# Tracking-Car.net
KiCad netlist of a schematic drawn in Altium Designer
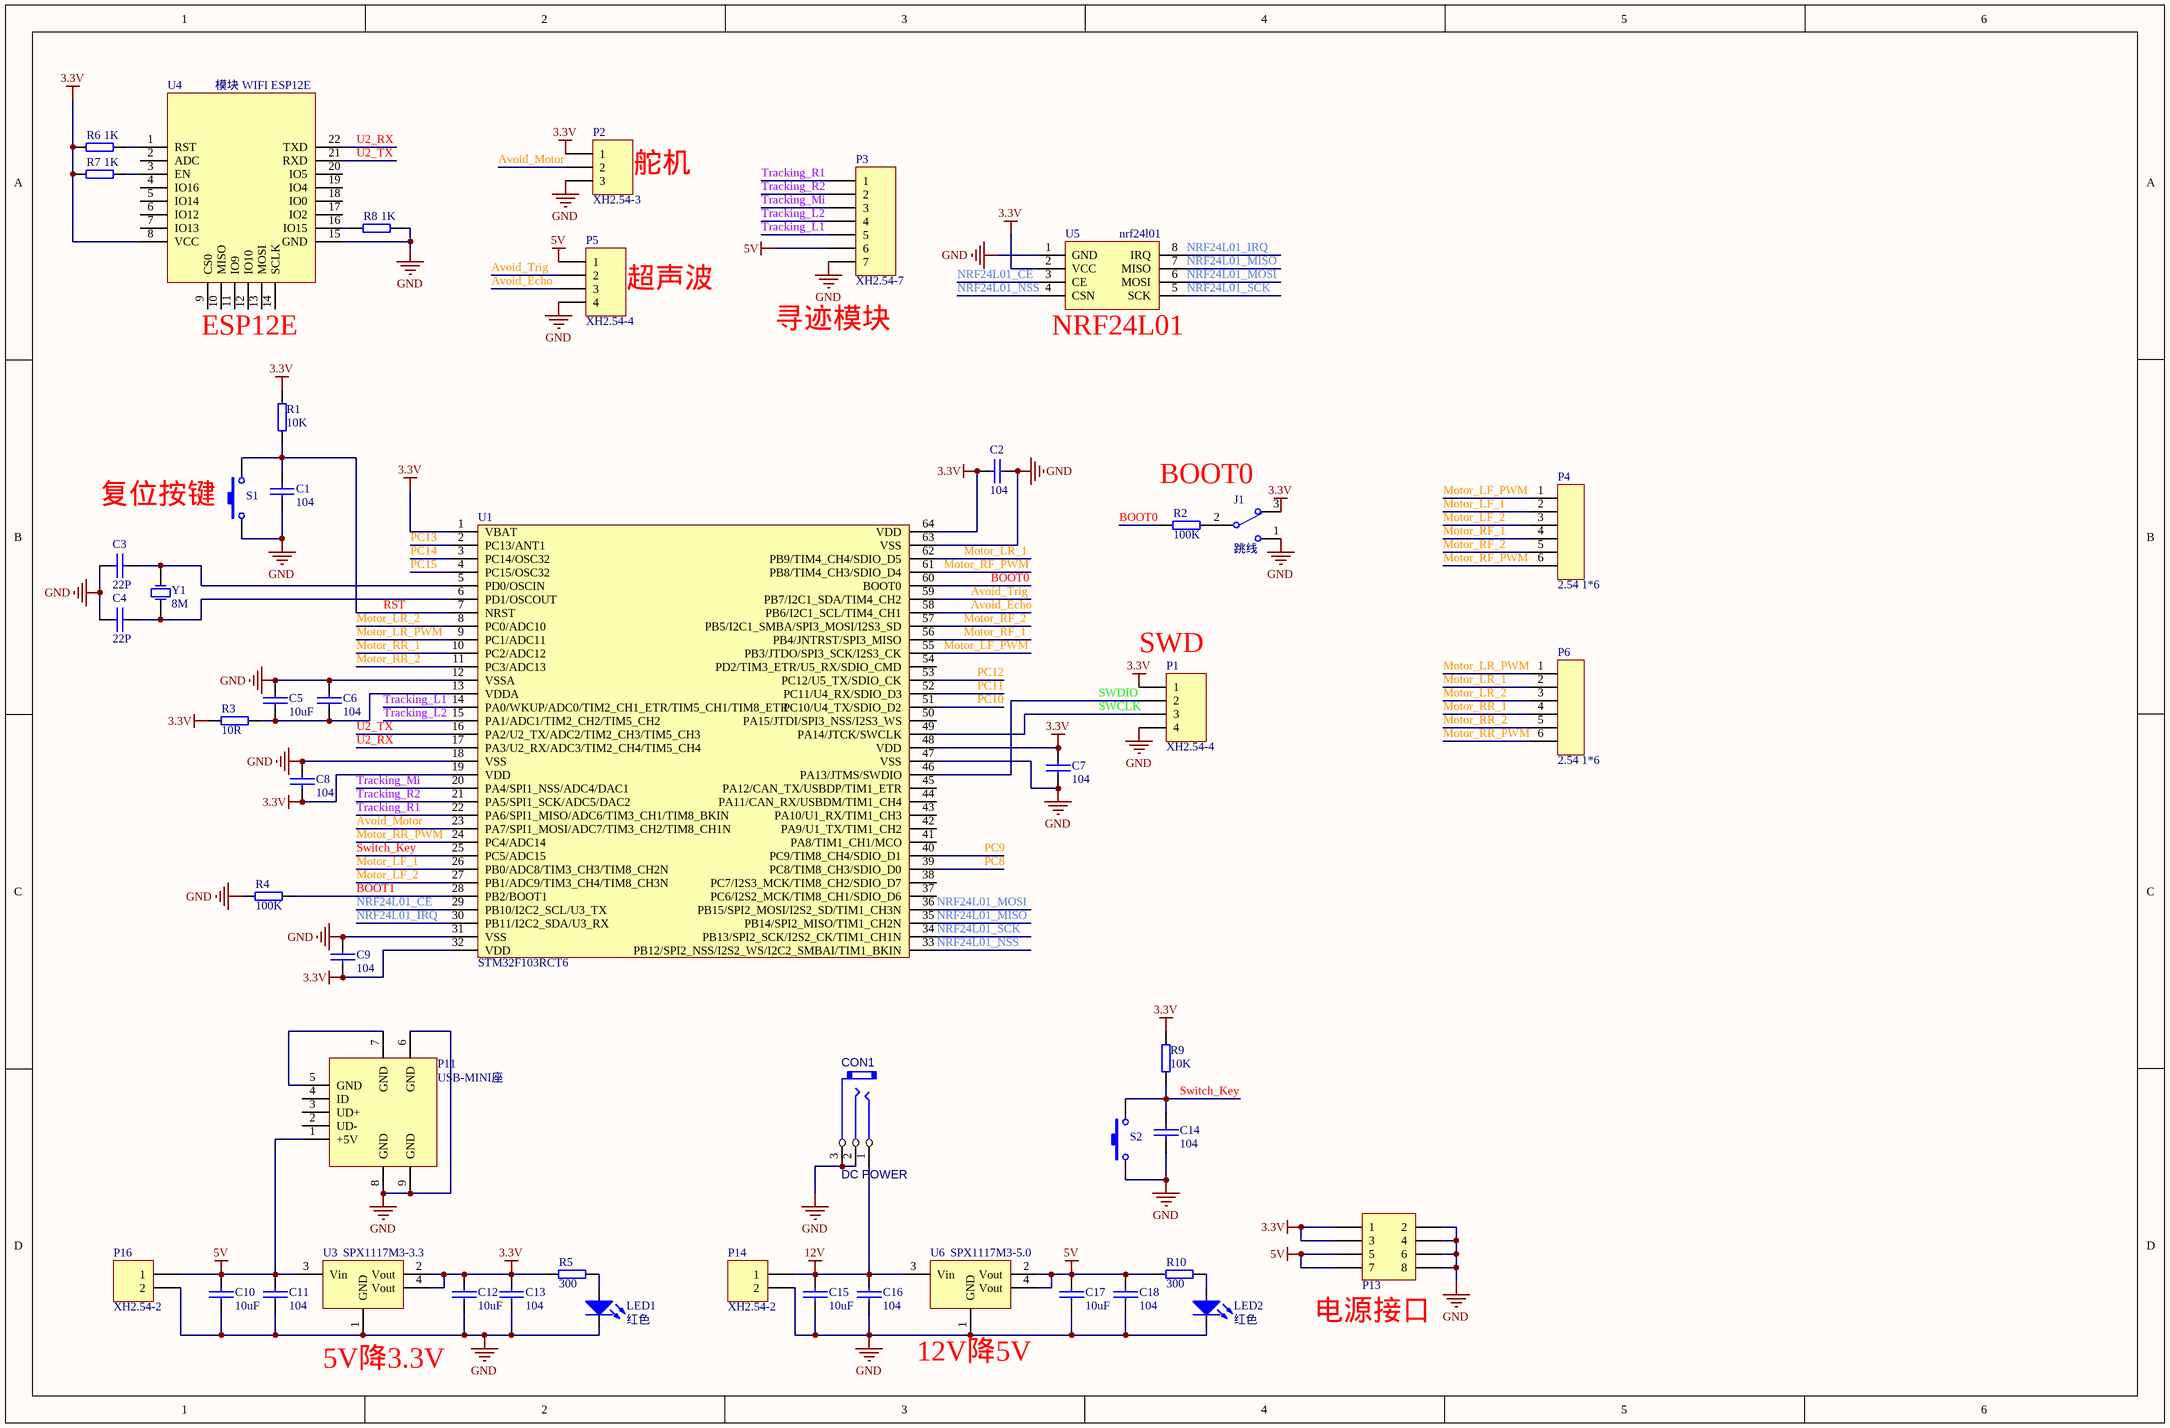
[diagram p0: Tracking-Car.SchDoc]

(export (version "E")
  (design (tool "Eeschema 10.0.6"))
  (components
    (comp (ref "C1")
      (value "104")
      (footprint "0805")
      (libsource (lib "Sch_Device_veryaz") (part "电容 贴片 0805"))
    )
    (comp (ref "C2")
      (value "104")
      (footprint "0805")
      (libsource (lib "Sch_Device_veryaz") (part "电容 贴片 0805"))
    )
    (comp (ref "C3")
      (value "22P")
      (footprint "0805")
      (libsource (lib "Sch_Device_veryaz") (part "电容 贴片 0805"))
    )
    (comp (ref "C4")
      (value "22P")
      (footprint "0805")
      (libsource (lib "Sch_Device_veryaz") (part "电容 贴片 0805"))
    )
    (comp (ref "C5")
      (value "10uF")
      (footprint "0805")
      (libsource (lib "Sch_Device_veryaz") (part "电容 贴片 0805"))
    )
    (comp (ref "C6")
      (value "104")
      (footprint "0805")
      (libsource (lib "Sch_Device_veryaz") (part "电容 贴片 0805"))
    )
    (comp (ref "C7")
      (value "104")
      (footprint "0805")
      (libsource (lib "Sch_Device_veryaz") (part "电容 贴片 0805"))
    )
    (comp (ref "C8")
      (value "104")
      (footprint "0805")
      (libsource (lib "Sch_Device_veryaz") (part "电容 贴片 0805"))
    )
    (comp (ref "C9")
      (value "104")
      (footprint "0805")
      (libsource (lib "Sch_Device_veryaz") (part "电容 贴片 0805"))
    )
    (comp (ref "C10")
      (value "10uF")
      (footprint "0805")
      (libsource (lib "Sch_Device_veryaz") (part "电容 贴片 0805"))
    )
    (comp (ref "C11")
      (value "104")
      (footprint "0805")
      (libsource (lib "Sch_Device_veryaz") (part "电容 贴片 0805"))
    )
    (comp (ref "C12")
      (value "10uF")
      (footprint "0805")
      (libsource (lib "Sch_Device_veryaz") (part "电容 贴片 0805"))
    )
    (comp (ref "C13")
      (value "104")
      (footprint "0805")
      (libsource (lib "Sch_Device_veryaz") (part "电容 贴片 0805"))
    )
    (comp (ref "C14")
      (value "104")
      (footprint "0805")
      (libsource (lib "Sch_Device_veryaz") (part "电容 贴片 0805"))
    )
    (comp (ref "C15")
      (value "10uF")
      (footprint "0805")
      (libsource (lib "Sch_Device_veryaz") (part "电容 贴片 0805"))
    )
    (comp (ref "C16")
      (value "104")
      (footprint "0805")
      (libsource (lib "Sch_Device_veryaz") (part "电容 贴片 0805"))
    )
    (comp (ref "C17")
      (value "10uF")
      (footprint "0805")
      (libsource (lib "Sch_Device_veryaz") (part "电容 贴片 0805"))
    )
    (comp (ref "C18")
      (value "104")
      (footprint "0805")
      (libsource (lib "Sch_Device_veryaz") (part "电容 贴片 0805"))
    )
    (comp (ref "CON1")
      (value "DC POWER")
      (footprint "Power  2.1mm")
      (libsource (lib "Sch_Device_veryaz") (part "连接件 电源座"))
    )
    (comp (ref "J1")
      (value "跳线")
      (footprint "单排插针 2.54 1*3")
      (libsource (lib "Sch_Device_veryaz") (part "联结件 跳线端子 2.54-3"))
    )
    (comp (ref "LED1")
      (value "红色")
      (footprint "LED0805")
      (libsource (lib "Sch_Device_veryaz") (part "二极管 贴片发光 0805"))
    )
    (comp (ref "LED2")
      (value "红色")
      (footprint "LED0805")
      (libsource (lib "Sch_Device_veryaz") (part "二极管 贴片发光 0805"))
    )
    (comp (ref "P1")
      (value "XH2.54-4")
      (footprint "VH2.54_4")
      (libsource (lib "Sch_Device_veryaz") (part "联结件 XH2.54-4"))
    )
    (comp (ref "P2")
      (value "XH2.54-3")
      (footprint "单排插针 2.54 1*3")
      (libsource (lib "Sch_Device_veryaz") (part "连接件 XH2.54-3"))
    )
    (comp (ref "P3")
      (value "XH2.54-7")
      (footprint "VH2.54_7")
      (libsource (lib "Sch_Device_veryaz") (part "连接件 XH2.54-7"))
    )
    (comp (ref "P4")
      (value "2.54 1*6")
      (footprint "单排插针 2.54 1*6")
      (libsource (lib "Sch_Device_veryaz") (part "连接件 单排插针 2.54 1*6"))
    )
    (comp (ref "P5")
      (value "XH2.54-4")
      (footprint "VH2.54_4")
      (libsource (lib "Sch_Device_veryaz") (part "联结件 XH2.54-4"))
    )
    (comp (ref "P6")
      (value "2.54 1*6")
      (footprint "单排插针 2.54 1*6")
      (libsource (lib "Sch_Device_veryaz") (part "连接件 单排插针 2.54 1*6"))
    )
    (comp (ref "P11")
      (value "USB-MINI座")
      (footprint "USB MINI DIP")
      (libsource (lib "Sch_Device_veryaz") (part "联结件 USB-MINI座"))
    )
    (comp (ref "P13")
      (value "双排插针 2.54 2*4")
      (footprint "双排插针 2.54 2*4")
      (libsource (lib "Sch_Device_veryaz") (part "联结件 双排插针 2.54 2*4"))
    )
    (comp (ref "P14")
      (value "XH2.54-2")
      (footprint "VH2.54_2")
      (libsource (lib "Sch_Device_veryaz") (part "联结件 XH2.54-2"))
    )
    (comp (ref "P16")
      (value "XH2.54-2")
      (footprint "VH2.54_2")
      (libsource (lib "Sch_Device_veryaz") (part "联结件 XH2.54-2"))
    )
    (comp (ref "R1") (value "10K") (footprint "0805") (libsource (lib "") (part "电阻 贴片 0805_1")))
    (comp (ref "R2")
      (value "100K")
      (footprint "0805")
      (libsource (lib "Sch_Device_veryaz") (part "电阻 贴片 0805"))
    )
    (comp (ref "R3")
      (value "10R")
      (footprint "0805")
      (libsource (lib "Sch_Device_veryaz") (part "电阻 贴片 0805"))
    )
    (comp (ref "R4")
      (value "100K")
      (footprint "0805")
      (libsource (lib "Sch_Device_veryaz") (part "电阻 贴片 0805"))
    )
    (comp (ref "R5")
      (value "300")
      (footprint "0805")
      (libsource (lib "Sch_Device_veryaz") (part "电阻 贴片 0805"))
    )
    (comp (ref "R6")
      (value "1K")
      (footprint "0805")
      (libsource (lib "Sch_Device_veryaz") (part "电阻 贴片 0805"))
    )
    (comp (ref "R7")
      (value "1K")
      (footprint "0805")
      (libsource (lib "Sch_Device_veryaz") (part "电阻 贴片 0805"))
    )
    (comp (ref "R8")
      (value "1K")
      (footprint "0805")
      (libsource (lib "Sch_Device_veryaz") (part "电阻 贴片 0805"))
    )
    (comp (ref "R9") (value "10K") (footprint "0805") (libsource (lib "") (part "电阻 贴片 0805_1")))
    (comp (ref "R10")
      (value "300")
      (footprint "0805")
      (libsource (lib "Sch_Device_veryaz") (part "电阻 贴片 0805"))
    )
    (comp (ref "S1")
      (value "key")
      (footprint "按键 轻触  6*3")
      (libsource (lib "Sch_Device_veryaz") (part "按键 轻触 3*6"))
    )
    (comp (ref "S2")
      (value "key")
      (footprint "按键 轻触  6*3")
      (libsource (lib "Sch_Device_veryaz") (part "按键 轻触 3*6"))
    )
    (comp (ref "U1")
      (value "STM32F103RCT6")
      (footprint "Pcb Device_veryaz:LQFP64")
      (description "单片机")
      (libsource (lib "Sch_Device_veryaz") (part "贴片芯片 STM32F103RCT6"))
    )
    (comp (ref "U3")
      (value "SPX1117M3-3.3")
      (footprint "SOT223")
      (description "LDO")
      (libsource (lib "Sch_Device_veryaz") (part "贴片芯片 SPX1117M3-3.3"))
    )
    (comp (ref "U4")
      (value "模块 WIFI ESP12E")
      (footprint "模块 WIFI ESP12E")
      (libsource (lib "Sch_Device_veryaz") (part "模块 WIFI ESP12E"))
    )
    (comp (ref "U5")
      (value "nrf24l01")
      (footprint "模块 NRF24L01")
      (libsource (lib "Sch_Device_veryaz") (part "模块 NRF24L01"))
    )
    (comp (ref "U6")
      (value "SPX1117M3-5.0")
      (footprint "SOT223")
      (description "LDO")
      (libsource (lib "Sch_Device_veryaz") (part "贴片芯片 SPX1117M3-5.0"))
    )
    (comp (ref "Y1")
      (value "8M")
      (footprint "晶振 BCY-W2/E4.7")
      (libsource (lib "Sch_Device_veryaz") (part "晶振 直插矮"))
    )
  )
  (nets
    (net (code "1") (name "/Avoid_Echo") (class "Default")
      (node (ref "P5") (pin "3") (pinfunction "3_3") (pintype "passive"))
      (node (ref "U1") (pin "58") (pinfunction "PB6/I2C1_SCL/TIM4_CH1_58") (pintype "passive"))
    )
    (net (code "2") (name "/Avoid_Motor") (class "Default")
      (node (ref "P2") (pin "2") (pinfunction "2_2") (pintype "passive"))
      (node (ref "U1") (pin "23") (pinfunction "PA7/SPI1_MOSI/ADC7/TIM3_CH2/TIM8_CH1N_23") (pintype "passive"))
    )
    (net (code "3") (name "/Avoid_Trig") (class "Default")
      (node (ref "P5") (pin "2") (pinfunction "2_2") (pintype "passive"))
      (node (ref "U1") (pin "59") (pinfunction "PB7/I2C1_SDA/TIM4_CH2_59") (pintype "passive"))
    )
    (net (code "4") (name "/BOOT0") (class "Default")
      (node (ref "R2") (pin "2") (pinfunction "2_2") (pintype "passive"))
      (node (ref "U1") (pin "60") (pinfunction "BOOT0_60") (pintype "passive"))
    )
    (net (code "5") (name "/BOOT1") (class "Default")
      (node (ref "R4") (pin "1") (pinfunction "1_1") (pintype "passive"))
      (node (ref "U1") (pin "28") (pinfunction "PB2/BOOT1_28") (pintype "passive"))
    )
    (net (code "6") (name "/Motor_LF_1") (class "Default")
      (node (ref "P4") (pin "2") (pinfunction "2_2") (pintype "passive"))
      (node (ref "U1") (pin "26") (pinfunction "PB0/ADC8/TIM3_CH3/TIM8_CH2N_26") (pintype "passive"))
    )
    (net (code "7") (name "/Motor_LF_2") (class "Default")
      (node (ref "P4") (pin "3") (pinfunction "3_3") (pintype "passive"))
      (node (ref "U1") (pin "27") (pinfunction "PB1/ADC9/TIM3_CH4/TIM8_CH3N_27") (pintype "passive"))
    )
    (net (code "8") (name "/Motor_LF_PWM") (class "Default")
      (node (ref "P4") (pin "1") (pinfunction "1_1") (pintype "passive"))
      (node (ref "U1") (pin "55") (pinfunction "PB3/JTDO/SPI3_SCK/I2S3_CK_55") (pintype "passive"))
    )
    (net (code "9") (name "/Motor_LR_1") (class "Default")
      (node (ref "P6") (pin "2") (pinfunction "2_2") (pintype "passive"))
      (node (ref "U1") (pin "62") (pinfunction "PB9/TIM4_CH4/SDIO_D5_62") (pintype "passive"))
    )
    (net (code "10") (name "/Motor_LR_2") (class "Default")
      (node (ref "P6") (pin "3") (pinfunction "3_3") (pintype "passive"))
      (node (ref "U1") (pin "8") (pinfunction "PC0/ADC10_8") (pintype "passive"))
    )
    (net (code "11") (name "/Motor_LR_PWM") (class "Default")
      (node (ref "P6") (pin "1") (pinfunction "1_1") (pintype "passive"))
      (node (ref "U1") (pin "9") (pinfunction "PC1/ADC11_9") (pintype "passive"))
    )
    (net (code "12") (name "/Motor_RF_1") (class "Default")
      (node (ref "P4") (pin "4") (pinfunction "4_4") (pintype "passive"))
      (node (ref "U1") (pin "56") (pinfunction "PB4/JNTRST/SPI3_MISO_56") (pintype "passive"))
    )
    (net (code "13") (name "/Motor_RF_2") (class "Default")
      (node (ref "P4") (pin "5") (pinfunction "5_5") (pintype "passive"))
      (node (ref "U1") (pin "57") (pinfunction "PB5/I2C1_SMBA/SPI3_MOSI/I2S3_SD_57") (pintype "passive"))
    )
    (net (code "14") (name "/Motor_RF_PWM") (class "Default")
      (node (ref "P4") (pin "6") (pinfunction "6_6") (pintype "passive"))
      (node (ref "U1") (pin "61") (pinfunction "PB8/TIM4_CH3/SDIO_D4_61") (pintype "passive"))
    )
    (net (code "15") (name "/Motor_RR_1") (class "Default")
      (node (ref "P6") (pin "4") (pinfunction "4_4") (pintype "passive"))
      (node (ref "U1") (pin "10") (pinfunction "PC2/ADC12_10") (pintype "passive"))
    )
    (net (code "16") (name "/Motor_RR_2") (class "Default")
      (node (ref "P6") (pin "5") (pinfunction "5_5") (pintype "passive"))
      (node (ref "U1") (pin "11") (pinfunction "PC3/ADC13_11") (pintype "passive"))
    )
    (net (code "17") (name "/Motor_RR_PWM") (class "Default")
      (node (ref "P6") (pin "6") (pinfunction "6_6") (pintype "passive"))
      (node (ref "U1") (pin "24") (pinfunction "PC4/ADC14_24") (pintype "passive"))
    )
    (net (code "18") (name "/NRF24L01_CE") (class "Default")
      (node (ref "U1") (pin "29") (pinfunction "PB10/I2C2_SCL/U3_TX_29") (pintype "passive"))
      (node (ref "U5") (pin "3") (pinfunction "CE_3") (pintype "passive"))
    )
    (net (code "19") (name "/NRF24L01_IRQ") (class "Default")
      (node (ref "U1") (pin "30") (pinfunction "PB11/I2C2_SDA/U3_RX_30") (pintype "passive"))
      (node (ref "U5") (pin "8") (pinfunction "IRQ_8") (pintype "passive"))
    )
    (net (code "20") (name "/NRF24L01_MISO") (class "Default")
      (node (ref "U1") (pin "35") (pinfunction "PB14/SPI2_MISO/TIM1_CH2N_35") (pintype "passive"))
      (node (ref "U5") (pin "7") (pinfunction "MISO_7") (pintype "passive"))
    )
    (net (code "21") (name "/NRF24L01_MOSI") (class "Default")
      (node (ref "U1") (pin "36") (pinfunction "PB15/SPI2_MOSI/I2S2_SD/TIM1_CH3N_36") (pintype "passive"))
      (node (ref "U5") (pin "6") (pinfunction "MOSI_6") (pintype "passive"))
    )
    (net (code "22") (name "/NRF24L01_NSS") (class "Default")
      (node (ref "U1") (pin "33") (pinfunction "PB12/SPI2_NSS/I2S2_WS/I2C2_SMBAI/TIM1_BKIN_33") (pintype "passive"))
      (node (ref "U5") (pin "4") (pinfunction "CSN_4") (pintype "passive"))
    )
    (net (code "23") (name "/NRF24L01_SCK") (class "Default")
      (node (ref "U1") (pin "34") (pinfunction "PB13/SPI2_SCK/I2S2_CK/TIM1_CH1N_34") (pintype "passive"))
      (node (ref "U5") (pin "5") (pinfunction "SCK_5") (pintype "passive"))
    )
    (net (code "24") (name "/PC8") (class "Default")
      (node (ref "U1") (pin "39") (pinfunction "PC8/TIM8_CH3/SDIO_D0_39") (pintype "passive"))
    )
    (net (code "25") (name "/PC9") (class "Default")
      (node (ref "U1") (pin "40") (pinfunction "PC9/TIM8_CH4/SDIO_D1_40") (pintype "passive"))
    )
    (net (code "26") (name "/PC10") (class "Default")
      (node (ref "U1") (pin "51") (pinfunction "PC10/U4_TX/SDIO_D2_51") (pintype "passive"))
    )
    (net (code "27") (name "/PC11") (class "Default")
      (node (ref "U1") (pin "52") (pinfunction "PC11/U4_RX/SDIO_D3_52") (pintype "passive"))
    )
    (net (code "28") (name "/PC12") (class "Default")
      (node (ref "U1") (pin "53") (pinfunction "PC12/U5_TX/SDIO_CK_53") (pintype "passive"))
    )
    (net (code "29") (name "/PC13") (class "Default")
      (node (ref "U1") (pin "2") (pinfunction "PC13/ANT1_2") (pintype "passive"))
    )
    (net (code "30") (name "/PC14") (class "Default")
      (node (ref "U1") (pin "3") (pinfunction "PC14/OSC32_3") (pintype "passive"))
    )
    (net (code "31") (name "/PC15") (class "Default")
      (node (ref "U1") (pin "4") (pinfunction "PC15/OSC32_4") (pintype "passive"))
    )
    (net (code "32") (name "/RST") (class "Default")
      (node (ref "C1") (pin "2") (pintype "passive"))
      (node (ref "R1") (pin "2") (pinfunction "2_2") (pintype "passive"))
      (node (ref "S1") (pin "2") (pinfunction "2_2") (pintype "passive"))
      (node (ref "U1") (pin "7") (pinfunction "NRST_7") (pintype "passive"))
    )
    (net (code "33") (name "/SWCLK") (class "Default")
      (node (ref "P1") (pin "3") (pinfunction "3_3") (pintype "passive"))
      (node (ref "U1") (pin "49") (pinfunction "PA14/JTCK/SWCLK_49") (pintype "passive"))
    )
    (net (code "34") (name "/SWDIO") (class "Default")
      (node (ref "P1") (pin "2") (pinfunction "2_2") (pintype "passive"))
      (node (ref "U1") (pin "46") (pinfunction "PA13/JTMS/SWDIO_46") (pintype "passive"))
    )
    (net (code "35") (name "/Switch_Key") (class "Default")
      (node (ref "C14") (pin "2") (pintype "passive"))
      (node (ref "R9") (pin "2") (pinfunction "2_2") (pintype "passive"))
      (node (ref "S2") (pin "2") (pinfunction "2_2") (pintype "passive"))
      (node (ref "U1") (pin "25") (pinfunction "PC5/ADC15_25") (pintype "passive"))
    )
    (net (code "36") (name "/Tracking_L1") (class "Default")
      (node (ref "P3") (pin "5") (pinfunction "5_5") (pintype "passive"))
      (node (ref "U1") (pin "14") (pinfunction "PA0/WKUP/ADC0/TIM2_CH1_ETR/TIM5_CH1/TIM8_ETR_14") (pintype "passive"))
    )
    (net (code "37") (name "/Tracking_L2") (class "Default")
      (node (ref "P3") (pin "4") (pinfunction "4_4") (pintype "passive"))
      (node (ref "U1") (pin "15") (pinfunction "PA1/ADC1/TIM2_CH2/TIM5_CH2_15") (pintype "passive"))
    )
    (net (code "38") (name "/Tracking_Mi") (class "Default")
      (node (ref "P3") (pin "3") (pinfunction "3_3") (pintype "passive"))
      (node (ref "U1") (pin "20") (pinfunction "PA4/SPI1_NSS/ADC4/DAC1_20") (pintype "passive"))
    )
    (net (code "39") (name "/Tracking_R1") (class "Default")
      (node (ref "P3") (pin "1") (pinfunction "1_1") (pintype "passive"))
      (node (ref "U1") (pin "22") (pinfunction "PA6/SPI1_MISO/ADC6/TIM3_CH1/TIM8_BKIN_22") (pintype "passive"))
    )
    (net (code "40") (name "/Tracking_R2") (class "Default")
      (node (ref "P3") (pin "2") (pinfunction "2_2") (pintype "passive"))
      (node (ref "U1") (pin "21") (pinfunction "PA5/SPI1_SCK/ADC5/DAC2_21") (pintype "passive"))
    )
    (net (code "41") (name "/U2_RX") (class "Default")
      (node (ref "U1") (pin "17") (pinfunction "PA3/U2_RX/ADC3/TIM2_CH4/TIM5_CH4_17") (pintype "passive"))
      (node (ref "U4") (pin "22") (pinfunction "TXD_22") (pintype "passive"))
    )
    (net (code "42") (name "/U2_TX") (class "Default")
      (node (ref "U1") (pin "16") (pinfunction "PA2/U2_TX/ADC2/TIM2_CH3/TIM5_CH3_16") (pintype "passive"))
      (node (ref "U4") (pin "21") (pinfunction "RXD_21") (pintype "passive"))
    )
    (net (code "43") (name "3.3V") (class "Default")
      (node (ref "C12") (pin "2") (pintype "passive"))
      (node (ref "C13") (pin "2") (pintype "passive"))
      (node (ref "C2") (pin "2") (pintype "passive"))
      (node (ref "C7") (pin "1") (pintype "passive"))
      (node (ref "C8") (pin "1") (pintype "passive"))
      (node (ref "C9") (pin "1") (pintype "passive"))
      (node (ref "J1") (pin "3") (pinfunction "3_3") (pintype "passive"))
      (node (ref "P1") (pin "1") (pinfunction "1_1") (pintype "passive"))
      (node (ref "P13") (pin "1") (pinfunction "1_1") (pintype "passive"))
      (node (ref "P13") (pin "3") (pinfunction "3_3") (pintype "passive"))
      (node (ref "P2") (pin "1") (pinfunction "1_1") (pintype "passive"))
      (node (ref "R1") (pin "1") (pinfunction "1_1") (pintype "passive"))
      (node (ref "R3") (pin "2") (pinfunction "2_2") (pintype "passive"))
      (node (ref "R5") (pin "2") (pinfunction "2_2") (pintype "passive"))
      (node (ref "R6") (pin "2") (pinfunction "2_2") (pintype "passive"))
      (node (ref "R7") (pin "2") (pinfunction "2_2") (pintype "passive"))
      (node (ref "R9") (pin "1") (pinfunction "1_1") (pintype "passive"))
      (node (ref "U1") (pin "1") (pinfunction "VBAT_1") (pintype "passive"))
      (node (ref "U1") (pin "19") (pinfunction "VDD_19") (pintype "passive"))
      (node (ref "U1") (pin "32") (pinfunction "VDD_32") (pintype "passive"))
      (node (ref "U1") (pin "48") (pinfunction "VDD_48") (pintype "passive"))
      (node (ref "U1") (pin "64") (pinfunction "VDD_64") (pintype "passive"))
      (node (ref "U3") (pin "2") (pinfunction "Vout_2") (pintype "passive"))
      (node (ref "U3") (pin "4") (pinfunction "Vout_4") (pintype "passive"))
      (node (ref "U4") (pin "8") (pinfunction "VCC_8") (pintype "passive"))
      (node (ref "U5") (pin "2") (pinfunction "VCC_2") (pintype "passive"))
    )
    (net (code "44") (name "5V") (class "Default")
      (node (ref "C10") (pin "2") (pintype "passive"))
      (node (ref "C11") (pin "2") (pintype "passive"))
      (node (ref "C17") (pin "2") (pintype "passive"))
      (node (ref "C18") (pin "2") (pintype "passive"))
      (node (ref "P11") (pin "1") (pinfunction "+5V_1") (pintype "passive"))
      (node (ref "P13") (pin "5") (pinfunction "5_5") (pintype "passive"))
      (node (ref "P13") (pin "7") (pinfunction "7_7") (pintype "passive"))
      (node (ref "P16") (pin "1") (pinfunction "1_1") (pintype "passive"))
      (node (ref "P3") (pin "6") (pinfunction "6_6") (pintype "passive"))
      (node (ref "P5") (pin "1") (pinfunction "1_1") (pintype "passive"))
      (node (ref "R10") (pin "2") (pinfunction "2_2") (pintype "passive"))
      (node (ref "U3") (pin "3") (pinfunction "Vin_3") (pintype "passive"))
      (node (ref "U6") (pin "2") (pinfunction "Vout_2") (pintype "passive"))
      (node (ref "U6") (pin "4") (pinfunction "Vout_4") (pintype "passive"))
    )
    (net (code "45") (name "12V") (class "Default")
      (node (ref "C15") (pin "2") (pintype "passive"))
      (node (ref "C16") (pin "2") (pintype "passive"))
      (node (ref "CON1") (pin "1") (pinfunction "1_1") (pintype "passive"))
      (node (ref "P14") (pin "1") (pinfunction "1_1") (pintype "passive"))
      (node (ref "U6") (pin "3") (pinfunction "Vin_3") (pintype "passive"))
    )
    (net (code "46") (name "GND") (class "Default")
      (node (ref "C1") (pin "1") (pintype "passive"))
      (node (ref "C10") (pin "1") (pintype "passive"))
      (node (ref "C11") (pin "1") (pintype "passive"))
      (node (ref "C12") (pin "1") (pintype "passive"))
      (node (ref "C13") (pin "1") (pintype "passive"))
      (node (ref "C14") (pin "1") (pintype "passive"))
      (node (ref "C15") (pin "1") (pintype "passive"))
      (node (ref "C16") (pin "1") (pintype "passive"))
      (node (ref "C17") (pin "1") (pintype "passive"))
      (node (ref "C18") (pin "1") (pintype "passive"))
      (node (ref "C2") (pin "1") (pintype "passive"))
      (node (ref "C3") (pin "1") (pintype "passive"))
      (node (ref "C4") (pin "1") (pintype "passive"))
      (node (ref "C5") (pin "2") (pintype "passive"))
      (node (ref "C6") (pin "2") (pintype "passive"))
      (node (ref "C7") (pin "2") (pintype "passive"))
      (node (ref "C8") (pin "2") (pintype "passive"))
      (node (ref "C9") (pin "2") (pintype "passive"))
      (node (ref "CON1") (pin "2") (pinfunction "2_2") (pintype "passive"))
      (node (ref "CON1") (pin "3") (pinfunction "3_3") (pintype "passive"))
      (node (ref "J1") (pin "1") (pinfunction "1_1") (pintype "passive"))
      (node (ref "LED1") (pin "2") (pinfunction "K_2") (pintype "passive"))
      (node (ref "LED2") (pin "2") (pinfunction "K_2") (pintype "passive"))
      (node (ref "P1") (pin "4") (pinfunction "4_4") (pintype "passive"))
      (node (ref "P11") (pin "6") (pinfunction "GND_6") (pintype "passive"))
      (node (ref "P11") (pin "8") (pinfunction "GND_8") (pintype "passive"))
      (node (ref "P11") (pin "9") (pinfunction "GND_9") (pintype "passive"))
      (node (ref "P13") (pin "2") (pinfunction "2_2") (pintype "passive"))
      (node (ref "P13") (pin "4") (pinfunction "4_4") (pintype "passive"))
      (node (ref "P13") (pin "6") (pinfunction "6_6") (pintype "passive"))
      (node (ref "P13") (pin "8") (pinfunction "8_8") (pintype "passive"))
      (node (ref "P14") (pin "2") (pinfunction "2_2") (pintype "passive"))
      (node (ref "P16") (pin "2") (pinfunction "2_2") (pintype "passive"))
      (node (ref "P2") (pin "3") (pinfunction "3_3") (pintype "passive"))
      (node (ref "P3") (pin "7") (pinfunction "7_7") (pintype "passive"))
      (node (ref "P5") (pin "4") (pinfunction "4_4") (pintype "passive"))
      (node (ref "R4") (pin "2") (pinfunction "2_2") (pintype "passive"))
      (node (ref "R8") (pin "1") (pinfunction "1_1") (pintype "passive"))
      (node (ref "S1") (pin "1") (pinfunction "1_1") (pintype "passive"))
      (node (ref "S2") (pin "1") (pinfunction "1_1") (pintype "passive"))
      (node (ref "U1") (pin "12") (pinfunction "VSSA_12") (pintype "passive"))
      (node (ref "U1") (pin "18") (pinfunction "VSS_18") (pintype "passive"))
      (node (ref "U1") (pin "31") (pinfunction "VSS_31") (pintype "passive"))
      (node (ref "U1") (pin "47") (pinfunction "VSS_47") (pintype "passive"))
      (node (ref "U1") (pin "63") (pinfunction "VSS_63") (pintype "passive"))
      (node (ref "U3") (pin "1") (pinfunction "GND_1") (pintype "passive"))
      (node (ref "U4") (pin "15") (pinfunction "GND_15") (pintype "passive"))
      (node (ref "U5") (pin "1") (pinfunction "GND_1") (pintype "passive"))
      (node (ref "U6") (pin "1") (pinfunction "GND_1") (pintype "passive"))
    )
    (net (code "47") (name "Net-(J1-Pad2)") (class "Default")
      (node (ref "J1") (pin "2") (pinfunction "2_2") (pintype "passive"))
      (node (ref "R2") (pin "1") (pinfunction "1_1") (pintype "passive"))
    )
    (net (code "48") (name "Net-(LED1-A)") (class "Default")
      (node (ref "LED1") (pin "1") (pinfunction "A_1") (pintype "passive"))
      (node (ref "R5") (pin "1") (pinfunction "1_1") (pintype "passive"))
    )
    (net (code "49") (name "Net-(LED2-A)") (class "Default")
      (node (ref "LED2") (pin "1") (pinfunction "A_1") (pintype "passive"))
      (node (ref "R10") (pin "1") (pinfunction "1_1") (pintype "passive"))
    )
    (net (code "50") (name "Net-(P11-GND-Pad5)") (class "Default")
      (node (ref "P11") (pin "5") (pinfunction "GND_5") (pintype "passive"))
      (node (ref "P11") (pin "7") (pinfunction "GND_7") (pintype "passive"))
    )
    (net (code "51") (name "Net-(U1-PD0{slash}OSCIN)") (class "Default")
      (node (ref "C3") (pin "2") (pintype "passive"))
      (node (ref "U1") (pin "5") (pinfunction "PD0/OSCIN_5") (pintype "passive"))
      (node (ref "Y1") (pin "2") (pinfunction "OSC2_2") (pintype "passive"))
    )
    (net (code "52") (name "Net-(U1-PD1{slash}OSCOUT)") (class "Default")
      (node (ref "C4") (pin "2") (pintype "passive"))
      (node (ref "U1") (pin "6") (pinfunction "PD1/OSCOUT_6") (pintype "passive"))
      (node (ref "Y1") (pin "1") (pinfunction "OSC1_1") (pintype "passive"))
    )
    (net (code "53") (name "Net-(U1-VDDA)") (class "Default")
      (node (ref "C5") (pin "1") (pintype "passive"))
      (node (ref "C6") (pin "1") (pintype "passive"))
      (node (ref "R3") (pin "1") (pinfunction "1_1") (pintype "passive"))
      (node (ref "U1") (pin "13") (pinfunction "VDDA_13") (pintype "passive"))
    )
    (net (code "54") (name "Net-(U4-EN)") (class "Default")
      (node (ref "R7") (pin "1") (pinfunction "1_1") (pintype "passive"))
      (node (ref "U4") (pin "3") (pinfunction "EN_3") (pintype "passive"))
    )
    (net (code "55") (name "Net-(U4-IO15)") (class "Default")
      (node (ref "R8") (pin "2") (pinfunction "2_2") (pintype "passive"))
      (node (ref "U4") (pin "16") (pinfunction "IO15_16") (pintype "passive"))
    )
    (net (code "56") (name "Net-(U4-RST)") (class "Default")
      (node (ref "R6") (pin "1") (pinfunction "1_1") (pintype "passive"))
      (node (ref "U4") (pin "1") (pinfunction "RST_1") (pintype "passive"))
    )
    (net (code "57") (name "unconnected-(P11-ID-Pad4)") (class "Default")
      (node (ref "P11") (pin "4") (pinfunction "ID_4") (pintype "passive"))
    )
    (net (code "58") (name "unconnected-(P11-UD+-Pad3)") (class "Default")
      (node (ref "P11") (pin "3") (pinfunction "UD+_3") (pintype "passive"))
    )
    (net (code "59") (name "unconnected-(P11-UD--Pad2)") (class "Default")
      (node (ref "P11") (pin "2") (pinfunction "UD-_2") (pintype "passive"))
    )
    (net (code "60") (name "unconnected-(U1-PA8{slash}TIM1_CH1{slash}MCO-Pad41)") (class "Default")
      (node (ref "U1") (pin "41") (pinfunction "PA8/TIM1_CH1/MCO_41") (pintype "passive"))
    )
    (net (code "61") (name "unconnected-(U1-PA9{slash}U1_TX{slash}TIM1_CH2-Pad42)") (class "Default")
      (node (ref "U1") (pin "42") (pinfunction "PA9/U1_TX/TIM1_CH2_42") (pintype "passive"))
    )
    (net (code "62") (name "unconnected-(U1-PA10{slash}U1_RX{slash}TIM1_CH3-Pad43)") (class "Default")
      (node (ref "U1") (pin "43") (pinfunction "PA10/U1_RX/TIM1_CH3_43") (pintype "passive"))
    )
    (net (code "63") (name "unconnected-(U1-PA11{slash}CAN_RX{slash}USBDM{slash}TIM1_CH4-Pad44)") (class "Default")
      (node (ref "U1") (pin "44") (pinfunction "PA11/CAN_RX/USBDM/TIM1_CH4_44") (pintype "passive"))
    )
    (net (code "64") (name "unconnected-(U1-PA12{slash}CAN_TX{slash}USBDP{slash}TIM1_ETR-Pad45)") (class "Default")
      (node (ref "U1") (pin "45") (pinfunction "PA12/CAN_TX/USBDP/TIM1_ETR_45") (pintype "passive"))
    )
    (net (code "65") (name "unconnected-(U1-PA15{slash}JTDI{slash}SPI3_NSS{slash}I2S3_WS-Pad50)") (class "Default")
      (node (ref "U1") (pin "50") (pinfunction "PA15/JTDI/SPI3_NSS/I2S3_WS_50") (pintype "passive"))
    )
    (net (code "66") (name "unconnected-(U1-PC6{slash}I2S2_MCK{slash}TIM8_CH1{slash}SDIO_D6-Pad37)") (class "Default")
      (node (ref "U1") (pin "37") (pinfunction "PC6/I2S2_MCK/TIM8_CH1/SDIO_D6_37") (pintype "passive"))
    )
    (net (code "67") (name "unconnected-(U1-PC7{slash}I2S3_MCK{slash}TIM8_CH2{slash}SDIO_D7-Pad38)") (class "Default")
      (node (ref "U1") (pin "38") (pinfunction "PC7/I2S3_MCK/TIM8_CH2/SDIO_D7_38") (pintype "passive"))
    )
    (net (code "68") (name "unconnected-(U1-PD2{slash}TIM3_ETR{slash}U5_RX{slash}SDIO_CMD-Pad54)") (class "Default")
      (node (ref "U1") (pin "54") (pinfunction "PD2/TIM3_ETR/U5_RX/SDIO_CMD_54") (pintype "passive"))
    )
    (net (code "69") (name "unconnected-(U4-ADC-Pad2)") (class "Default")
      (node (ref "U4") (pin "2") (pinfunction "ADC_2") (pintype "passive"))
    )
    (net (code "70") (name "unconnected-(U4-CS0-Pad9)") (class "Default")
      (node (ref "U4") (pin "9") (pinfunction "CS0_9") (pintype "passive"))
    )
    (net (code "71") (name "unconnected-(U4-IO0-Pad18)") (class "Default")
      (node (ref "U4") (pin "18") (pinfunction "IO0_18") (pintype "passive"))
    )
    (net (code "72") (name "unconnected-(U4-IO2-Pad17)") (class "Default")
      (node (ref "U4") (pin "17") (pinfunction "IO2_17") (pintype "passive"))
    )
    (net (code "73") (name "unconnected-(U4-IO4-Pad19)") (class "Default")
      (node (ref "U4") (pin "19") (pinfunction "IO4_19") (pintype "passive"))
    )
    (net (code "74") (name "unconnected-(U4-IO5-Pad20)") (class "Default")
      (node (ref "U4") (pin "20") (pinfunction "IO5_20") (pintype "passive"))
    )
    (net (code "75") (name "unconnected-(U4-IO9-Pad11)") (class "Default")
      (node (ref "U4") (pin "11") (pinfunction "IO9_11") (pintype "passive"))
    )
    (net (code "76") (name "unconnected-(U4-IO10-Pad12)") (class "Default")
      (node (ref "U4") (pin "12") (pinfunction "IO10_12") (pintype "passive"))
    )
    (net (code "77") (name "unconnected-(U4-IO12-Pad6)") (class "Default")
      (node (ref "U4") (pin "6") (pinfunction "IO12_6") (pintype "passive"))
    )
    (net (code "78") (name "unconnected-(U4-IO13-Pad7)") (class "Default")
      (node (ref "U4") (pin "7") (pinfunction "IO13_7") (pintype "passive"))
    )
    (net (code "79") (name "unconnected-(U4-IO14-Pad5)") (class "Default")
      (node (ref "U4") (pin "5") (pinfunction "IO14_5") (pintype "passive"))
    )
    (net (code "80") (name "unconnected-(U4-IO16-Pad4)") (class "Default")
      (node (ref "U4") (pin "4") (pinfunction "IO16_4") (pintype "passive"))
    )
    (net (code "81") (name "unconnected-(U4-MISO-Pad10)") (class "Default")
      (node (ref "U4") (pin "10") (pinfunction "MISO_10") (pintype "passive"))
    )
    (net (code "82") (name "unconnected-(U4-MOSI-Pad13)") (class "Default")
      (node (ref "U4") (pin "13") (pinfunction "MOSI_13") (pintype "passive"))
    )
    (net (code "83") (name "unconnected-(U4-SCLK-Pad14)") (class "Default")
      (node (ref "U4") (pin "14") (pinfunction "SCLK_14") (pintype "passive"))
    )
  )
)
